# ClockClock_Proto_X40.net
KiCad netlist of a schematic drawn in EAGLE
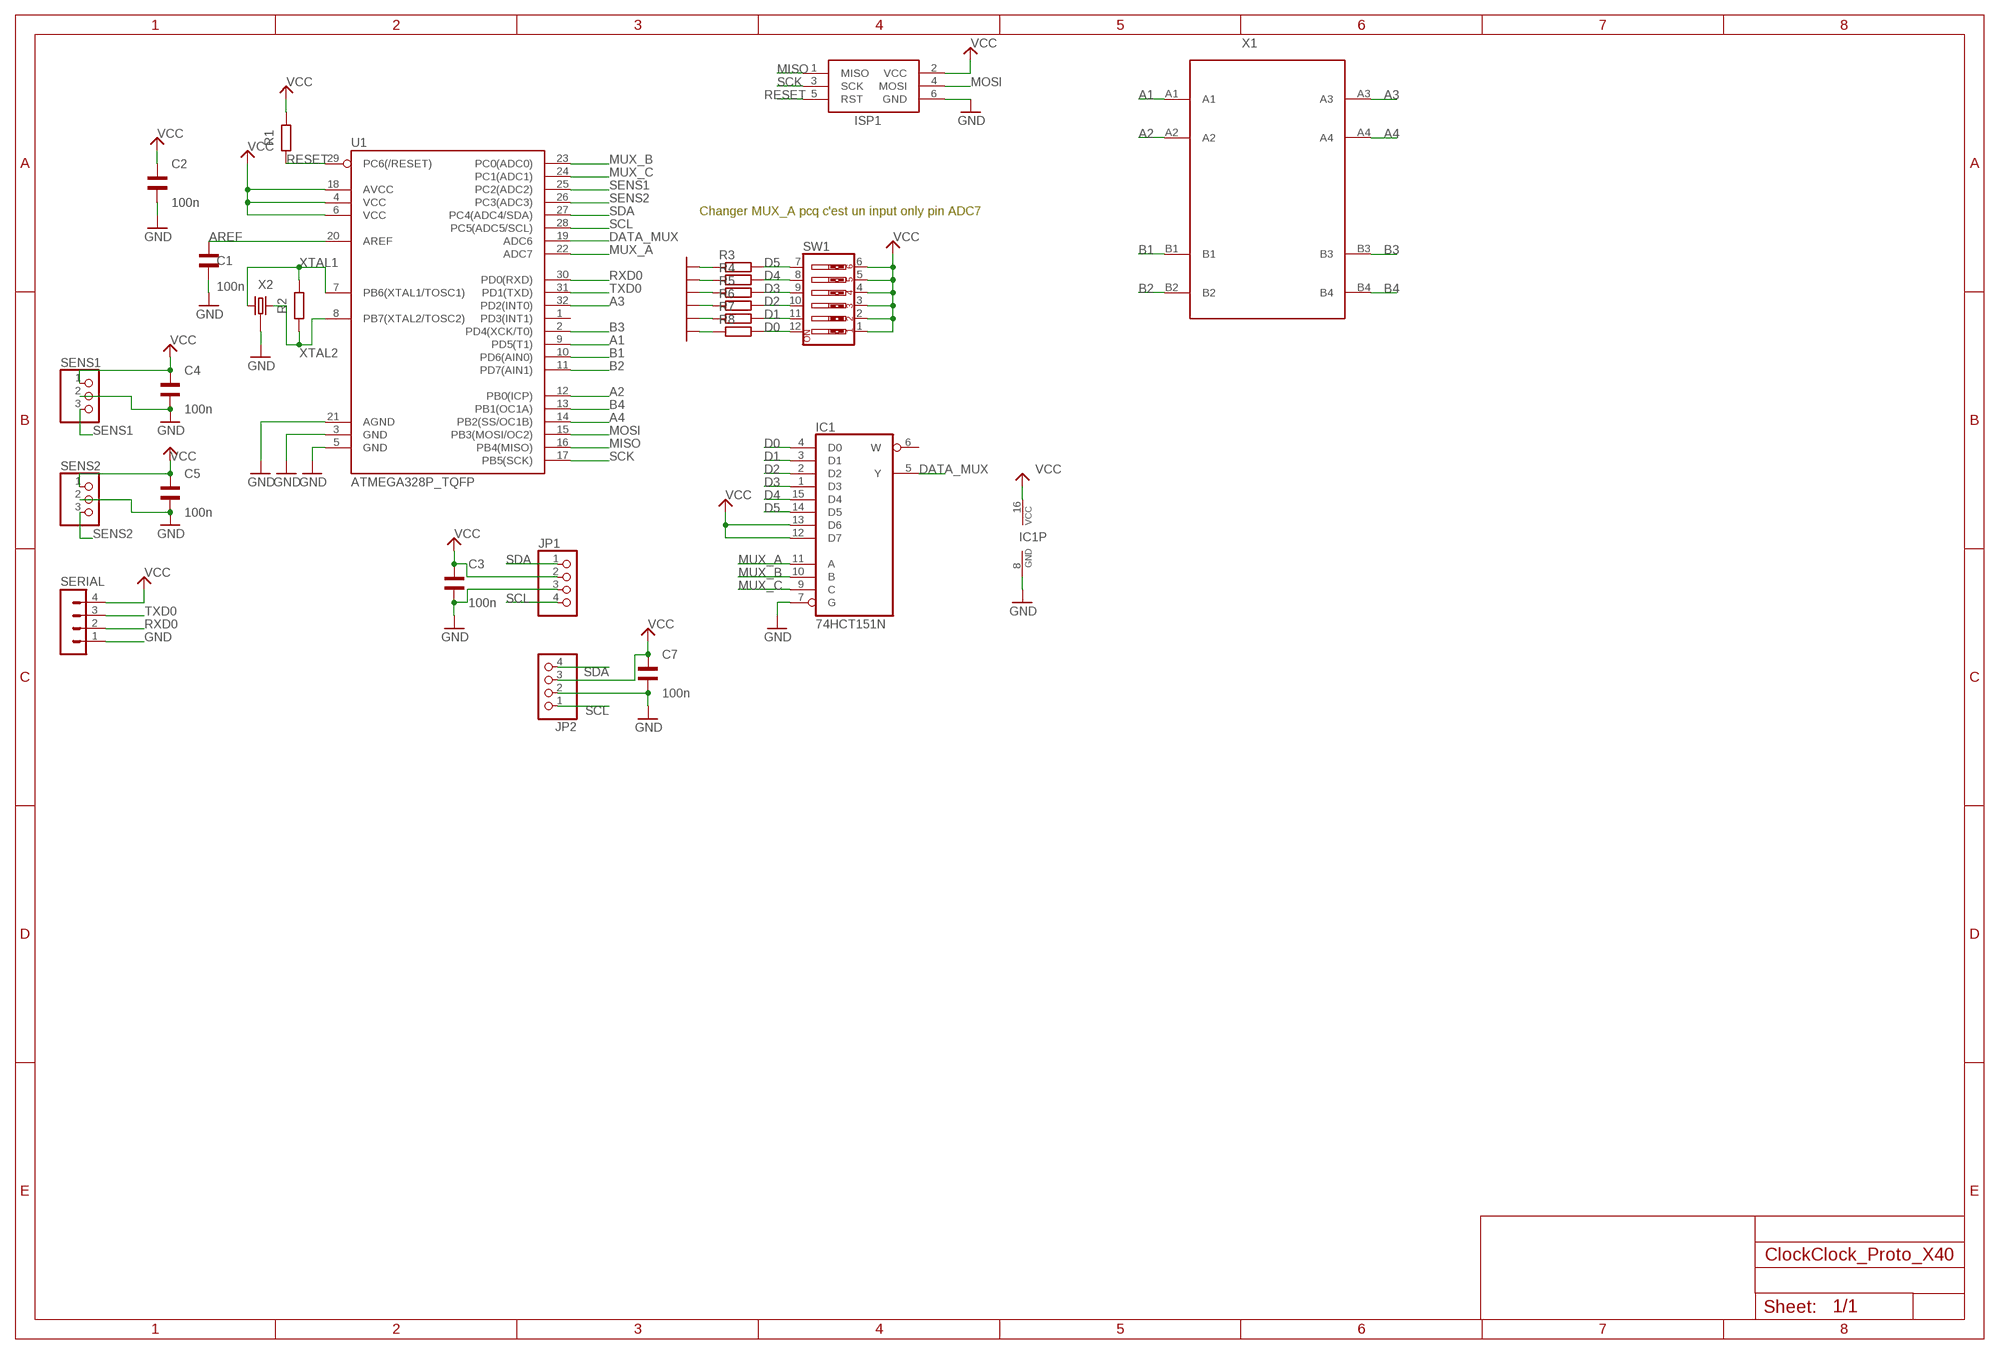
[diagram p0: schematic, sheet 1]

(export (version "E")
  (design (tool "Eeschema 10.0.6"))
  (components
    (comp (ref "C1")
      (value "100n")
      (footprint "eagle-import:WCAP-CSMH_1206_WAVE")
      (libsource (lib "eagle-import") (part "WCAP-CSMH_1206_WAVE_885342208002"))
    )
    (comp (ref "C2")
      (value "100n")
      (footprint "eagle-import:WCAP-CSMH_1206_WAVE")
      (libsource (lib "eagle-import") (part "WCAP-CSMH_1206_WAVE_885342208002"))
    )
    (comp (ref "C3")
      (value "100n")
      (footprint "eagle-import:WCAP-CSMH_1206_WAVE")
      (libsource (lib "eagle-import") (part "WCAP-CSMH_1206_WAVE_885342208002"))
    )
    (comp (ref "C4")
      (value "100n")
      (footprint "eagle-import:WCAP-CSMH_1206_WAVE")
      (libsource (lib "eagle-import") (part "WCAP-CSMH_1206_WAVE_885342208002"))
    )
    (comp (ref "C5")
      (value "100n")
      (footprint "eagle-import:WCAP-CSMH_1206_WAVE")
      (libsource (lib "eagle-import") (part "WCAP-CSMH_1206_WAVE_885342208002"))
    )
    (comp (ref "C7")
      (value "100n")
      (footprint "eagle-import:WCAP-CSMH_1206_WAVE")
      (libsource (lib "eagle-import") (part "WCAP-CSMH_1206_WAVE_885342208002"))
    )
    (comp (ref "IC1")
      (value "74HCT151N")
      (footprint "eagle-import:DIL16")
      (libsource (lib "eagle-import") (part "74151NHCT"))
    )
    (comp (ref "ISP1")
      (value "AVRISP-6")
      (footprint "eagle-import:AVRISP")
      (libsource (lib "eagle-import") (part "AVRISP-6"))
    )
    (comp (ref "JP1")
      (value "PINHD-1X4/90")
      (footprint "eagle-import:1X04_90")
      (libsource (lib "eagle-import") (part "PINHD-1X4/90"))
    )
    (comp (ref "JP2")
      (value "PINHD-1X4/90")
      (footprint "eagle-import:1X04_90")
      (libsource (lib "eagle-import") (part "PINHD-1X4/90"))
    )
    (comp (ref "R1")
      (value "15k")
      (footprint "eagle-import:R1206")
      (libsource (lib "eagle-import") (part "R-EU_R1206"))
    )
    (comp (ref "R2")
      (value "1M")
      (footprint "eagle-import:R0805")
      (libsource (lib "eagle-import") (part "R-EU_R0805"))
    )
    (comp (ref "R3")
      (value "R-EU_R1206")
      (footprint "eagle-import:R1206")
      (libsource (lib "eagle-import") (part "R-EU_R1206"))
    )
    (comp (ref "R4")
      (value "R-EU_R1206")
      (footprint "eagle-import:R1206")
      (libsource (lib "eagle-import") (part "R-EU_R1206"))
    )
    (comp (ref "R5")
      (value "R-EU_R1206")
      (footprint "eagle-import:R1206")
      (libsource (lib "eagle-import") (part "R-EU_R1206"))
    )
    (comp (ref "R6")
      (value "R-EU_R1206")
      (footprint "eagle-import:R1206")
      (libsource (lib "eagle-import") (part "R-EU_R1206"))
    )
    (comp (ref "R7")
      (value "R-EU_R1206")
      (footprint "eagle-import:R1206")
      (libsource (lib "eagle-import") (part "R-EU_R1206"))
    )
    (comp (ref "R8")
      (value "R-EU_R1206")
      (footprint "eagle-import:R1206")
      (libsource (lib "eagle-import") (part "R-EU_R1206"))
    )
    (comp (ref "SENS1")
      (value "PINHD-1X3")
      (footprint "eagle-import:1X03")
      (libsource (lib "eagle-import") (part "PINHD-1X3"))
    )
    (comp (ref "SENS2")
      (value "PINHD-1X3")
      (footprint "eagle-import:1X03")
      (libsource (lib "eagle-import") (part "PINHD-1X3"))
    )
    (comp (ref "SERIAL")
      (value "MA04-1")
      (footprint "eagle-import:MA04-1")
      (libsource (lib "eagle-import") (part "MA04-1"))
    )
    (comp (ref "SW1")
      (value "SWITCH_DIP-6_90")
      (footprint "eagle-import:DIP6_SWITCH_90DEG")
      (libsource (lib "eagle-import") (part "SWITCH_DIP-6_90"))
    )
    (comp (ref "U1")
      (value "ATMEGA328P_TQFP")
      (footprint "eagle-import:TQFP32-08")
      (libsource (lib "eagle-import") (part "ATMEGA328P_TQFP"))
    )
    (comp (ref "X1")
      (value "X40_MOTOR")
      (footprint "eagle-import:X40_MOTOR")
      (libsource (lib "eagle-import") (part "X40_MOTOR"))
    )
    (comp (ref "X2")
      (value "AEL_ZTT_RESONATOR_16M")
      (footprint "eagle-import:AEL_ZTT_RESONATOR")
      (libsource (lib "eagle-import") (part "AEL_ZTT_RESONATOR_16M"))
    )
  )
  (nets
    (net (code "1") (name "/A1") (class "Default")
      (node (ref "U1") (pin "9") (pinfunction "PD5(T1)_9") (pintype "bidirectional"))
      (node (ref "X1") (pin "A1") (pinfunction "A1_A1") (pintype "bidirectional"))
    )
    (net (code "2") (name "/A2") (class "Default")
      (node (ref "U1") (pin "12") (pinfunction "PB0(ICP)_12") (pintype "bidirectional"))
      (node (ref "X1") (pin "A2") (pinfunction "A2_A2") (pintype "bidirectional"))
    )
    (net (code "3") (name "/A3") (class "Default")
      (node (ref "U1") (pin "32") (pinfunction "PD2(INT0)_32") (pintype "bidirectional"))
      (node (ref "X1") (pin "A3") (pinfunction "A3_A3") (pintype "bidirectional"))
    )
    (net (code "4") (name "/A4") (class "Default")
      (node (ref "U1") (pin "14") (pinfunction "PB2(SS/OC1B)_14") (pintype "bidirectional"))
      (node (ref "X1") (pin "A4") (pinfunction "A4_A4") (pintype "bidirectional"))
    )
    (net (code "5") (name "/AREF") (class "Default")
      (node (ref "C1") (pin "2") (pinfunction "2_2") (pintype "passive"))
      (node (ref "U1") (pin "20") (pinfunction "AREF_20") (pintype "bidirectional"))
    )
    (net (code "6") (name "/B1") (class "Default")
      (node (ref "U1") (pin "10") (pinfunction "PD6(AIN0)_10") (pintype "bidirectional"))
      (node (ref "X1") (pin "B1") (pinfunction "B1_B1") (pintype "bidirectional"))
    )
    (net (code "7") (name "/B2") (class "Default")
      (node (ref "U1") (pin "11") (pinfunction "PD7(AIN1)_11") (pintype "bidirectional"))
      (node (ref "X1") (pin "B2") (pinfunction "B2_B2") (pintype "bidirectional"))
    )
    (net (code "8") (name "/B3") (class "Default")
      (node (ref "U1") (pin "2") (pinfunction "PD4(XCK/T0)_2") (pintype "bidirectional"))
      (node (ref "X1") (pin "B3") (pinfunction "B3_B3") (pintype "bidirectional"))
    )
    (net (code "9") (name "/B4") (class "Default")
      (node (ref "U1") (pin "13") (pinfunction "PB1(OC1A)_13") (pintype "bidirectional"))
      (node (ref "X1") (pin "B4") (pinfunction "B4_B4") (pintype "bidirectional"))
    )
    (net (code "10") (name "/D0") (class "Default")
      (node (ref "IC1") (pin "4") (pinfunction "D0_4") (pintype "input"))
      (node (ref "R8") (pin "2") (pinfunction "2_2") (pintype "passive"))
      (node (ref "SW1") (pin "12") (pinfunction "12_12") (pintype "passive"))
    )
    (net (code "11") (name "/D1") (class "Default")
      (node (ref "IC1") (pin "3") (pinfunction "D1_3") (pintype "input"))
      (node (ref "R7") (pin "2") (pinfunction "2_2") (pintype "passive"))
      (node (ref "SW1") (pin "11") (pinfunction "11_11") (pintype "passive"))
    )
    (net (code "12") (name "/D2") (class "Default")
      (node (ref "IC1") (pin "2") (pinfunction "D2_2") (pintype "input"))
      (node (ref "R6") (pin "2") (pinfunction "2_2") (pintype "passive"))
      (node (ref "SW1") (pin "10") (pinfunction "10_10") (pintype "passive"))
    )
    (net (code "13") (name "/D3") (class "Default")
      (node (ref "IC1") (pin "1") (pinfunction "D3_1") (pintype "input"))
      (node (ref "R5") (pin "2") (pinfunction "2_2") (pintype "passive"))
      (node (ref "SW1") (pin "9") (pinfunction "9_9") (pintype "passive"))
    )
    (net (code "14") (name "/D4") (class "Default")
      (node (ref "IC1") (pin "15") (pinfunction "D4_15") (pintype "input"))
      (node (ref "R4") (pin "2") (pinfunction "2_2") (pintype "passive"))
      (node (ref "SW1") (pin "8") (pinfunction "8_8") (pintype "passive"))
    )
    (net (code "15") (name "/D5") (class "Default")
      (node (ref "IC1") (pin "14") (pinfunction "D5_14") (pintype "input"))
      (node (ref "R3") (pin "2") (pinfunction "2_2") (pintype "passive"))
      (node (ref "SW1") (pin "7") (pinfunction "7_7") (pintype "passive"))
    )
    (net (code "16") (name "/DATA_MUX") (class "Default")
      (node (ref "IC1") (pin "5") (pinfunction "Y_5") (pintype "output"))
      (node (ref "U1") (pin "19") (pinfunction "ADC6_19") (pintype "bidirectional"))
    )
    (net (code "17") (name "/MISO") (class "Default")
      (node (ref "ISP1") (pin "1") (pinfunction "MISO_1") (pintype "input"))
      (node (ref "U1") (pin "16") (pinfunction "PB4(MISO)_16") (pintype "bidirectional"))
    )
    (net (code "18") (name "/MOSI") (class "Default")
      (node (ref "ISP1") (pin "4") (pinfunction "MOSI_4") (pintype "output"))
      (node (ref "U1") (pin "15") (pinfunction "PB3(MOSI/OC2)_15") (pintype "bidirectional"))
    )
    (net (code "19") (name "/MUX_A") (class "Default")
      (node (ref "IC1") (pin "11") (pinfunction "A_11") (pintype "input"))
      (node (ref "U1") (pin "22") (pinfunction "ADC7_22") (pintype "bidirectional"))
    )
    (net (code "20") (name "/MUX_B") (class "Default")
      (node (ref "IC1") (pin "10") (pinfunction "B_10") (pintype "input"))
      (node (ref "U1") (pin "23") (pinfunction "PC0(ADC0)_23") (pintype "bidirectional"))
    )
    (net (code "21") (name "/MUX_C") (class "Default")
      (node (ref "IC1") (pin "9") (pinfunction "C_9") (pintype "input"))
      (node (ref "U1") (pin "24") (pinfunction "PC1(ADC1)_24") (pintype "bidirectional"))
    )
    (net (code "22") (name "/RESET") (class "Default")
      (node (ref "ISP1") (pin "5") (pinfunction "RST_5") (pintype "output"))
      (node (ref "R1") (pin "1") (pinfunction "1_1") (pintype "passive"))
      (node (ref "U1") (pin "29") (pinfunction "PC6(/RESET)_29") (pintype "bidirectional"))
    )
    (net (code "23") (name "/RXD0") (class "Default")
      (node (ref "SERIAL") (pin "2") (pinfunction "2_2") (pintype "passive"))
      (node (ref "U1") (pin "30") (pinfunction "PD0(RXD)_30") (pintype "bidirectional"))
    )
    (net (code "24") (name "/SCK") (class "Default")
      (node (ref "ISP1") (pin "3") (pinfunction "SCK_3") (pintype "output"))
      (node (ref "U1") (pin "17") (pinfunction "PB5(SCK)_17") (pintype "bidirectional"))
    )
    (net (code "25") (name "/SCL") (class "Default")
      (node (ref "JP1") (pin "4") (pinfunction "4_4") (pintype "passive"))
      (node (ref "JP2") (pin "1") (pinfunction "1_1") (pintype "passive"))
      (node (ref "U1") (pin "28") (pinfunction "PC5(ADC5/SCL)_28") (pintype "bidirectional"))
    )
    (net (code "26") (name "/SDA") (class "Default")
      (node (ref "JP1") (pin "1") (pinfunction "1_1") (pintype "passive"))
      (node (ref "JP2") (pin "4") (pinfunction "4_4") (pintype "passive"))
      (node (ref "U1") (pin "27") (pinfunction "PC4(ADC4/SDA)_27") (pintype "bidirectional"))
    )
    (net (code "27") (name "/SENS1") (class "Default")
      (node (ref "SENS1") (pin "3") (pinfunction "3_3") (pintype "passive"))
      (node (ref "U1") (pin "25") (pinfunction "PC2(ADC2)_25") (pintype "bidirectional"))
    )
    (net (code "28") (name "/SENS2") (class "Default")
      (node (ref "SENS2") (pin "3") (pinfunction "3_3") (pintype "passive"))
      (node (ref "U1") (pin "26") (pinfunction "PC3(ADC3)_26") (pintype "bidirectional"))
    )
    (net (code "29") (name "/TXD0") (class "Default")
      (node (ref "SERIAL") (pin "3") (pinfunction "3_3") (pintype "passive"))
      (node (ref "U1") (pin "31") (pinfunction "PD1(TXD)_31") (pintype "bidirectional"))
    )
    (net (code "30") (name "/XTAL1") (class "Default")
      (node (ref "R2") (pin "2") (pinfunction "2_2") (pintype "passive"))
      (node (ref "U1") (pin "7") (pinfunction "PB6(XTAL1/TOSC1)_7") (pintype "bidirectional"))
      (node (ref "X2") (pin "P$1") (pinfunction "1_P$1") (pintype "passive"))
    )
    (net (code "31") (name "/XTAL2") (class "Default")
      (node (ref "R2") (pin "1") (pinfunction "1_1") (pintype "passive"))
      (node (ref "U1") (pin "8") (pinfunction "PB7(XTAL2/TOSC2)_8") (pintype "bidirectional"))
      (node (ref "X2") (pin "P$3") (pinfunction "2_P$3") (pintype "passive"))
    )
    (net (code "32") (name "5V") (class "Default")
      (node (ref "C2") (pin "2") (pinfunction "2_2") (pintype "passive"))
      (node (ref "C3") (pin "2") (pinfunction "2_2") (pintype "passive"))
      (node (ref "C4") (pin "2") (pinfunction "2_2") (pintype "passive"))
      (node (ref "C5") (pin "2") (pinfunction "2_2") (pintype "passive"))
      (node (ref "C7") (pin "2") (pinfunction "2_2") (pintype "passive"))
      (node (ref "IC1") (pin "12") (pinfunction "D7_12") (pintype "input"))
      (node (ref "IC1") (pin "13") (pinfunction "D6_13") (pintype "input"))
      (node (ref "IC1") (pin "16") (pinfunction "VCC_16") (pintype "power_in"))
      (node (ref "ISP1") (pin "2") (pinfunction "VCC_2") (pintype "power_in"))
      (node (ref "JP1") (pin "2") (pinfunction "2_2") (pintype "passive"))
      (node (ref "JP2") (pin "3") (pinfunction "3_3") (pintype "passive"))
      (node (ref "R1") (pin "2") (pinfunction "2_2") (pintype "passive"))
      (node (ref "SENS1") (pin "1") (pinfunction "1_1") (pintype "passive"))
      (node (ref "SENS2") (pin "1") (pinfunction "1_1") (pintype "passive"))
      (node (ref "SERIAL") (pin "4") (pinfunction "4_4") (pintype "passive"))
      (node (ref "SW1") (pin "1") (pinfunction "1_1") (pintype "passive"))
      (node (ref "SW1") (pin "2") (pinfunction "2_2") (pintype "passive"))
      (node (ref "SW1") (pin "3") (pinfunction "3_3") (pintype "passive"))
      (node (ref "SW1") (pin "4") (pinfunction "4_4") (pintype "passive"))
      (node (ref "SW1") (pin "5") (pinfunction "5_5") (pintype "passive"))
      (node (ref "SW1") (pin "6") (pinfunction "6_6") (pintype "passive"))
      (node (ref "U1") (pin "18") (pinfunction "AVCC_18") (pintype "bidirectional"))
      (node (ref "U1") (pin "4") (pinfunction "VCC_4") (pintype "bidirectional"))
      (node (ref "U1") (pin "6") (pinfunction "VCC_6") (pintype "bidirectional"))
    )
    (net (code "33") (name "GND") (class "Default")
      (node (ref "C1") (pin "1") (pinfunction "1_1") (pintype "passive"))
      (node (ref "C2") (pin "1") (pinfunction "1_1") (pintype "passive"))
      (node (ref "C3") (pin "1") (pinfunction "1_1") (pintype "passive"))
      (node (ref "C4") (pin "1") (pinfunction "1_1") (pintype "passive"))
      (node (ref "C5") (pin "1") (pinfunction "1_1") (pintype "passive"))
      (node (ref "C7") (pin "1") (pinfunction "1_1") (pintype "passive"))
      (node (ref "IC1") (pin "7") (pinfunction "G_7") (pintype "input"))
      (node (ref "IC1") (pin "8") (pinfunction "GND_8") (pintype "power_in"))
      (node (ref "ISP1") (pin "6") (pinfunction "GND_6") (pintype "power_in"))
      (node (ref "JP1") (pin "3") (pinfunction "3_3") (pintype "passive"))
      (node (ref "JP2") (pin "2") (pinfunction "2_2") (pintype "passive"))
      (node (ref "R3") (pin "1") (pinfunction "1_1") (pintype "passive"))
      (node (ref "R4") (pin "1") (pinfunction "1_1") (pintype "passive"))
      (node (ref "R5") (pin "1") (pinfunction "1_1") (pintype "passive"))
      (node (ref "R6") (pin "1") (pinfunction "1_1") (pintype "passive"))
      (node (ref "R7") (pin "1") (pinfunction "1_1") (pintype "passive"))
      (node (ref "R8") (pin "1") (pinfunction "1_1") (pintype "passive"))
      (node (ref "SENS1") (pin "2") (pinfunction "2_2") (pintype "passive"))
      (node (ref "SENS2") (pin "2") (pinfunction "2_2") (pintype "passive"))
      (node (ref "SERIAL") (pin "1") (pinfunction "1_1") (pintype "passive"))
      (node (ref "U1") (pin "21") (pinfunction "AGND_21") (pintype "bidirectional"))
      (node (ref "U1") (pin "3") (pinfunction "GND_3") (pintype "bidirectional"))
      (node (ref "U1") (pin "5") (pinfunction "GND_5") (pintype "bidirectional"))
      (node (ref "X2") (pin "GND") (pinfunction "GND_GND") (pintype "passive"))
    )
    (net (code "34") (name "unconnected-(IC1A-W-Pad6)") (class "Default")
      (node (ref "IC1") (pin "6") (pinfunction "W_6") (pintype "output"))
    )
    (net (code "35") (name "unconnected-(U1-PD3(INT1)-Pad1)") (class "Default")
      (node (ref "U1") (pin "1") (pinfunction "PD3(INT1)_1") (pintype "bidirectional"))
    )
  )
)
